# xiaochequdongban.net
KiCad netlist of a schematic drawn in Altium Designer
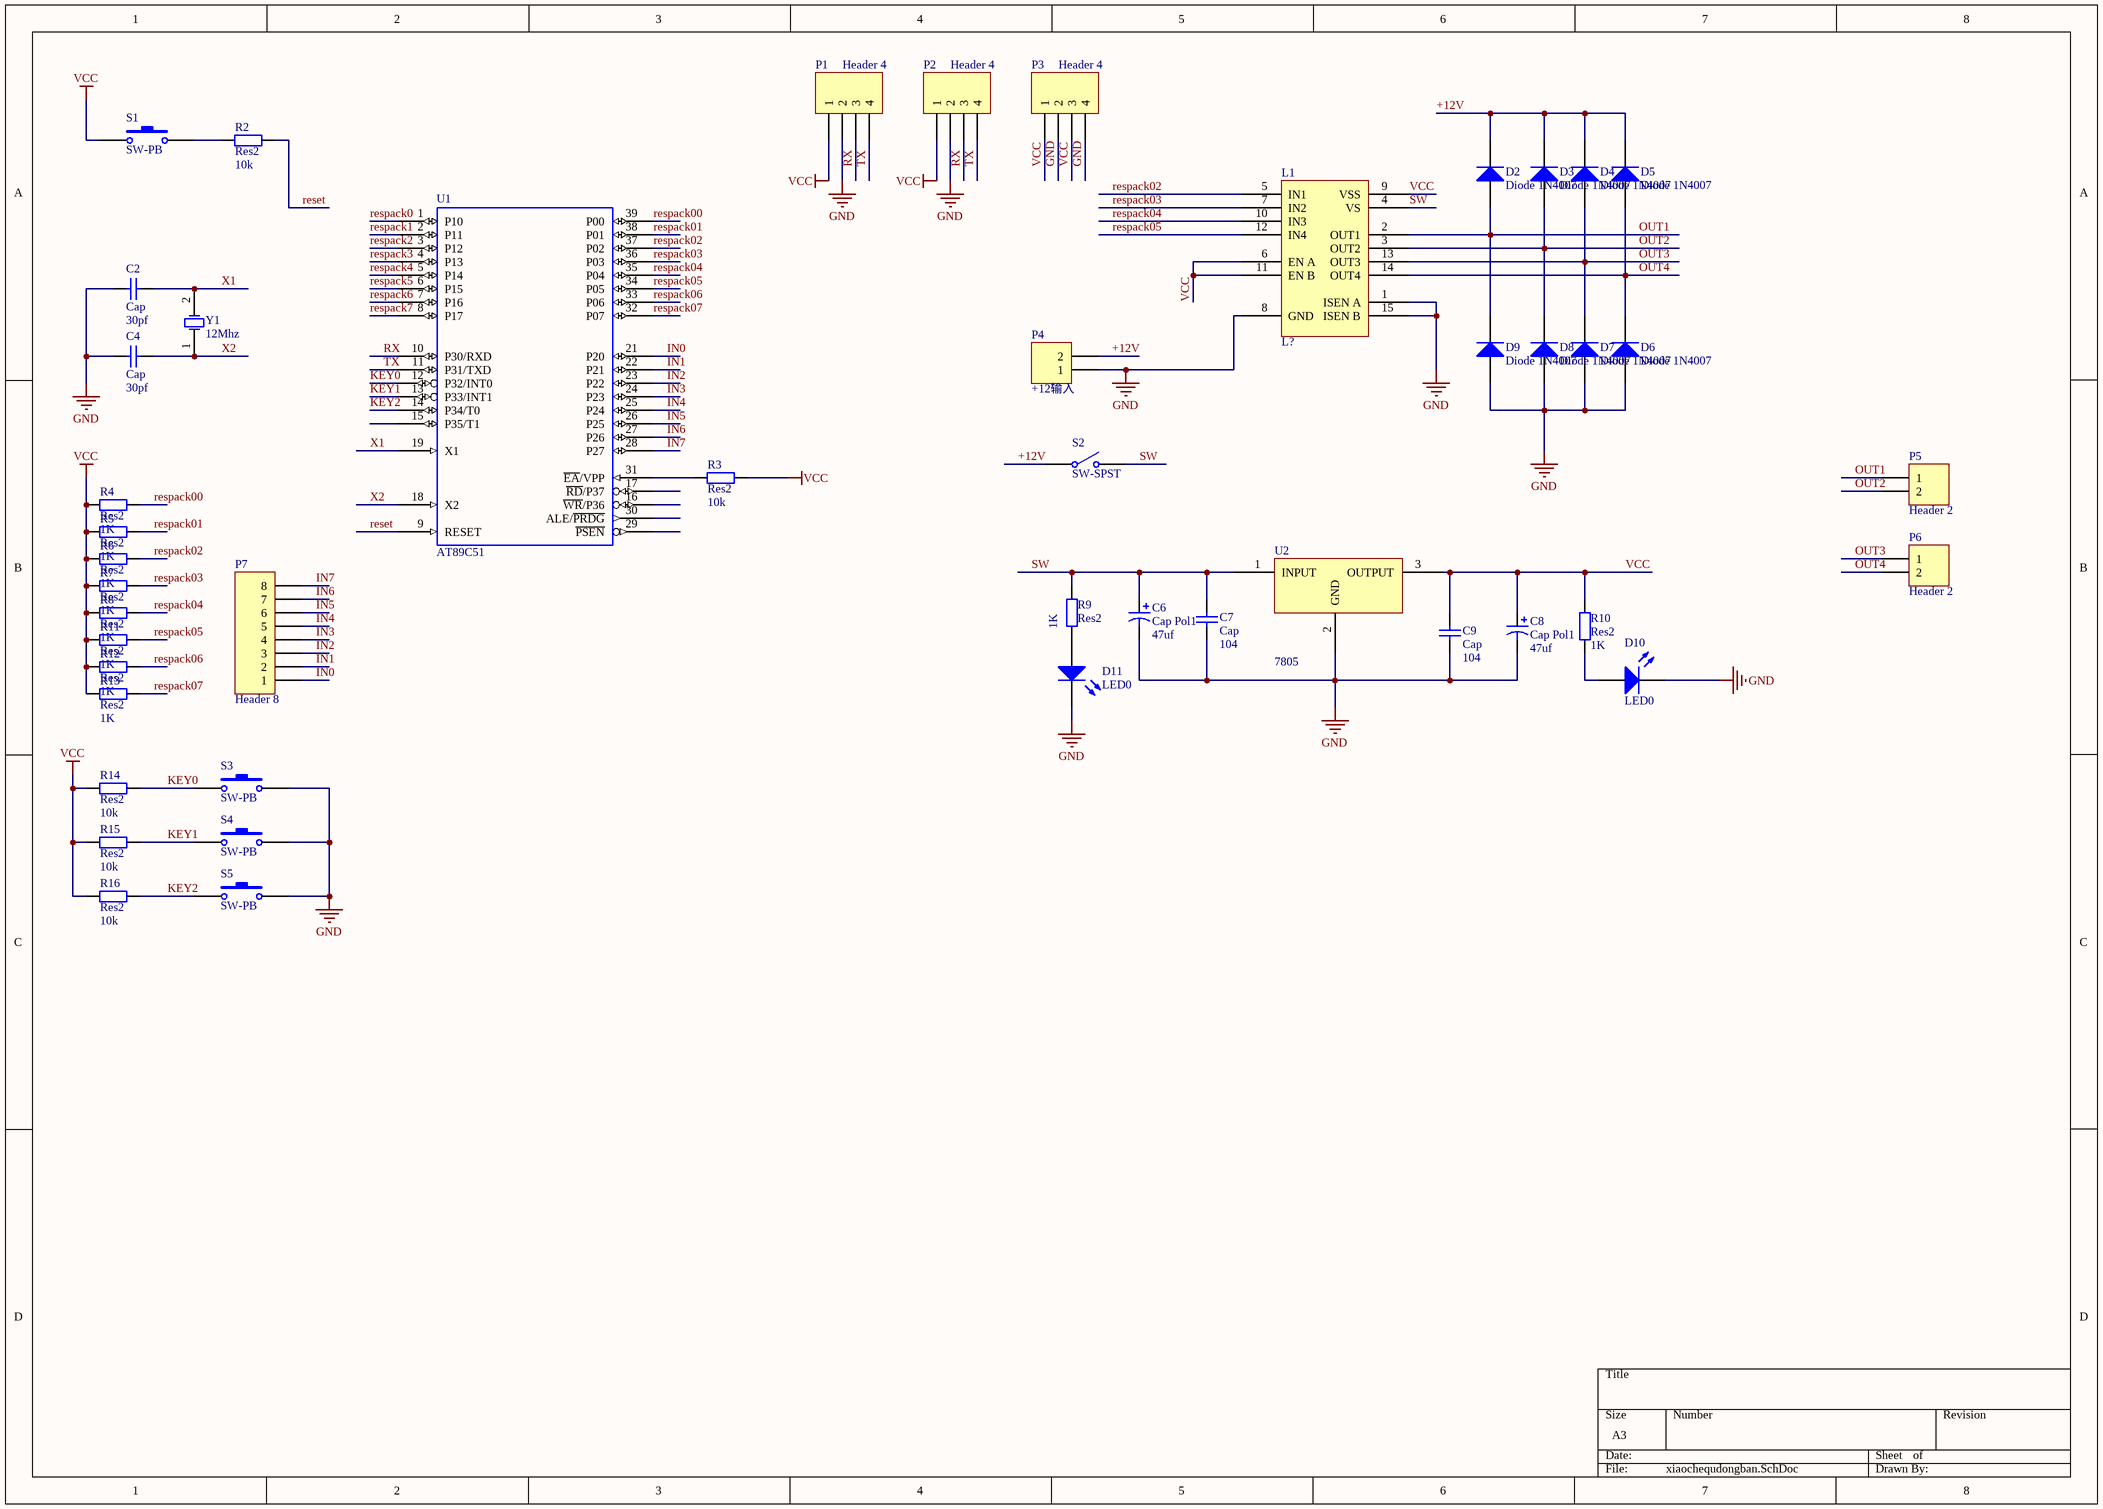
[diagram p0: xiaochequdongban.SchDoc]

(export (version "E")
  (design (tool "Eeschema 10.0.6"))
  (components
    (comp (ref "C2")
      (value "Cap")
      (footprint "RAD0.1")
      (description "Capacitor")
      (fields (field (name "ALTIUM_VALUE") "30pf") (field (name "PUBLISHER") "Altium Limited"))
      (libsource (lib "Miscellaneous Devices") (part "Cap"))
    )
    (comp (ref "C4")
      (value "Cap")
      (footprint "RAD0.1")
      (description "Capacitor")
      (fields (field (name "ALTIUM_VALUE") "30pf") (field (name "PUBLISHER") "Altium Limited"))
      (libsource (lib "Miscellaneous Devices") (part "Cap"))
    )
    (comp (ref "C6")
      (value "Cap Pol1")
      (footprint "CAP-E")
      (description "Polarized Capacitor (Radial)")
      (fields (field (name "ALTIUM_VALUE") "47uf") (field (name "PUBLISHER") "Altium Limited"))
      (libsource (lib "Miscellaneous Devices") (part "Cap Pol1"))
    )
    (comp (ref "C7")
      (value "Cap")
      (footprint "RAD0.1")
      (description "Capacitor")
      (fields (field (name "ALTIUM_VALUE") "104") (field (name "PUBLISHER") "Altium Limited"))
      (libsource (lib "Miscellaneous Devices") (part "Cap"))
    )
    (comp (ref "C8")
      (value "Cap Pol1")
      (footprint "CAP-E")
      (description "Polarized Capacitor (Radial)")
      (fields (field (name "ALTIUM_VALUE") "47uf") (field (name "PUBLISHER") "Altium Limited"))
      (libsource (lib "Miscellaneous Devices") (part "Cap Pol1"))
    )
    (comp (ref "C9")
      (value "Cap")
      (footprint "RAD0.1")
      (description "Capacitor")
      (fields (field (name "ALTIUM_VALUE") "104") (field (name "PUBLISHER") "Altium Limited"))
      (libsource (lib "Miscellaneous Devices") (part "Cap"))
    )
    (comp (ref "D2")
      (value "Diode 1N4007")
      (footprint "DO-41")
      (description "1 Amp General Purpose Rectifier")
      (fields (field (name "PUBLISHER") "Altium Limited"))
      (libsource (lib "Miscellaneous Devices") (part "Diode 1N4007"))
    )
    (comp (ref "D3")
      (value "Diode 1N4007")
      (footprint "DO-41")
      (description "1 Amp General Purpose Rectifier")
      (fields (field (name "PUBLISHER") "Altium Limited"))
      (libsource (lib "Miscellaneous Devices") (part "Diode 1N4007"))
    )
    (comp (ref "D4")
      (value "Diode 1N4007")
      (footprint "DO-41")
      (description "1 Amp General Purpose Rectifier")
      (fields (field (name "PUBLISHER") "Altium Limited"))
      (libsource (lib "Miscellaneous Devices") (part "Diode 1N4007"))
    )
    (comp (ref "D5")
      (value "Diode 1N4007")
      (footprint "DO-41")
      (description "1 Amp General Purpose Rectifier")
      (fields (field (name "PUBLISHER") "Altium Limited"))
      (libsource (lib "Miscellaneous Devices") (part "Diode 1N4007"))
    )
    (comp (ref "D6")
      (value "Diode 1N4007")
      (footprint "DO-41")
      (description "1 Amp General Purpose Rectifier")
      (fields (field (name "PUBLISHER") "Altium Limited"))
      (libsource (lib "Miscellaneous Devices") (part "Diode 1N4007"))
    )
    (comp (ref "D7")
      (value "Diode 1N4007")
      (footprint "DO-41")
      (description "1 Amp General Purpose Rectifier")
      (fields (field (name "PUBLISHER") "Altium Limited"))
      (libsource (lib "Miscellaneous Devices") (part "Diode 1N4007"))
    )
    (comp (ref "D8")
      (value "Diode 1N4007")
      (footprint "DO-41")
      (description "1 Amp General Purpose Rectifier")
      (fields (field (name "PUBLISHER") "Altium Limited"))
      (libsource (lib "Miscellaneous Devices") (part "Diode 1N4007"))
    )
    (comp (ref "D9")
      (value "Diode 1N4007")
      (footprint "DO-41")
      (description "1 Amp General Purpose Rectifier")
      (fields (field (name "PUBLISHER") "Altium Limited"))
      (libsource (lib "Miscellaneous Devices") (part "Diode 1N4007"))
    )
    (comp (ref "D10")
      (value "LED0")
      (footprint "LED")
      (description "Typical INFRARED GaAs LED")
      (fields (field (name "PUBLISHER") "Altium Limited"))
      (libsource (lib "Miscellaneous Devices") (part "LED0"))
    )
    (comp (ref "D11")
      (value "LED0")
      (footprint "LED")
      (description "Typical INFRARED GaAs LED")
      (fields (field (name "PUBLISHER") "Altium Limited"))
      (libsource (lib "Miscellaneous Devices") (part "LED0"))
    )
    (comp (ref "L1") (value "L?") (footprint "L298N") (libsource (lib "常用封装") (part "L298N")))
    (comp (ref "P1")
      (value "Header 4")
      (footprint "HDR1X4")
      (description "Header, 4-Pin")
      (fields (field (name "PUBLISHER") "Altium Limited"))
      (libsource (lib "Miscellaneous Connectors") (part "Header 4"))
    )
    (comp (ref "P2")
      (value "Header 4")
      (footprint "HDR1X4")
      (description "Header, 4-Pin")
      (fields (field (name "PUBLISHER") "Altium Limited"))
      (libsource (lib "Miscellaneous Connectors") (part "Header 4"))
    )
    (comp (ref "P3")
      (value "Header 4")
      (footprint "HDR1X4")
      (description "Header, 4-Pin")
      (fields (field (name "PUBLISHER") "Altium Limited"))
      (libsource (lib "Miscellaneous Connectors") (part "Header 4"))
    )
    (comp (ref "P4")
      (value "+12输入")
      (footprint "HDR1X2")
      (description "Header, 2-Pin")
      (fields (field (name "PUBLISHER") "Altium Limited"))
      (libsource (lib "Miscellaneous Connectors") (part "Header 2"))
    )
    (comp (ref "P5")
      (value "Header 2")
      (footprint "SIP2")
      (description "Header, 2-Pin")
      (fields (field (name "PUBLISHER") "Altium Limited"))
      (libsource (lib "") (part "Header 2_1"))
    )
    (comp (ref "P6")
      (value "Header 2")
      (footprint "HDR1X2")
      (description "Header, 2-Pin")
      (fields (field (name "PUBLISHER") "Altium Limited"))
      (libsource (lib "") (part "Header 2_1"))
    )
    (comp (ref "P7")
      (value "Header 8")
      (footprint "HDR1X8")
      (description "Header, 8-Pin")
      (fields (field (name "PUBLISHER") "Altium Limited"))
      (libsource (lib "Miscellaneous Connectors") (part "Header 8"))
    )
    (comp (ref "R2")
      (value "Res2")
      (footprint "0805")
      (description "Resistor")
      (fields (field (name "ALTIUM_VALUE") "10k") (field (name "PUBLISHER") "Altium Limited"))
      (libsource (lib "") (part "Res2_2"))
    )
    (comp (ref "R3")
      (value "Res2")
      (footprint "0805")
      (description "Resistor")
      (fields (field (name "ALTIUM_VALUE") "10k") (field (name "PUBLISHER") "Altium Limited"))
      (libsource (lib "") (part "Res2_2"))
    )
    (comp (ref "R4")
      (value "Res2")
      (footprint "0805")
      (description "Resistor")
      (fields (field (name "ALTIUM_VALUE") "1K") (field (name "PUBLISHER") "Altium Limited"))
      (libsource (lib "") (part "Res2_2"))
    )
    (comp (ref "R5")
      (value "Res2")
      (footprint "0805")
      (description "Resistor")
      (fields (field (name "ALTIUM_VALUE") "1K") (field (name "PUBLISHER") "Altium Limited"))
      (libsource (lib "") (part "Res2_2"))
    )
    (comp (ref "R6")
      (value "Res2")
      (footprint "0805")
      (description "Resistor")
      (fields (field (name "ALTIUM_VALUE") "1K") (field (name "PUBLISHER") "Altium Limited"))
      (libsource (lib "") (part "Res2_2"))
    )
    (comp (ref "R7")
      (value "Res2")
      (footprint "0805")
      (description "Resistor")
      (fields (field (name "ALTIUM_VALUE") "1K") (field (name "PUBLISHER") "Altium Limited"))
      (libsource (lib "") (part "Res2_2"))
    )
    (comp (ref "R8")
      (value "Res2")
      (footprint "0805")
      (description "Resistor")
      (fields (field (name "ALTIUM_VALUE") "1K") (field (name "PUBLISHER") "Altium Limited"))
      (libsource (lib "") (part "Res2_2"))
    )
    (comp (ref "R9")
      (value "Res2")
      (footprint "AXIAL0.3")
      (description "Resistor")
      (fields (field (name "ALTIUM_VALUE") "1K") (field (name "PUBLISHER") "Altium Limited"))
      (libsource (lib "") (part "Res2_1"))
    )
    (comp (ref "R10")
      (value "Res2")
      (footprint "0805")
      (description "Resistor")
      (fields (field (name "ALTIUM_VALUE") "1K") (field (name "PUBLISHER") "Altium Limited"))
      (libsource (lib "") (part "Res2_1"))
    )
    (comp (ref "R11")
      (value "Res2")
      (footprint "0805")
      (description "Resistor")
      (fields (field (name "ALTIUM_VALUE") "1K") (field (name "PUBLISHER") "Altium Limited"))
      (libsource (lib "") (part "Res2_2"))
    )
    (comp (ref "R12")
      (value "Res2")
      (footprint "0805")
      (description "Resistor")
      (fields (field (name "ALTIUM_VALUE") "1K") (field (name "PUBLISHER") "Altium Limited"))
      (libsource (lib "") (part "Res2_2"))
    )
    (comp (ref "R13")
      (value "Res2")
      (footprint "0805")
      (description "Resistor")
      (fields (field (name "ALTIUM_VALUE") "1K") (field (name "PUBLISHER") "Altium Limited"))
      (libsource (lib "") (part "Res2_2"))
    )
    (comp (ref "R14")
      (value "Res2")
      (footprint "0805")
      (description "Resistor")
      (fields (field (name "ALTIUM_VALUE") "10k") (field (name "PUBLISHER") "Altium Limited"))
      (libsource (lib "Miscellaneous Devices") (part "Res2"))
    )
    (comp (ref "R15")
      (value "Res2")
      (footprint "0805")
      (description "Resistor")
      (fields (field (name "ALTIUM_VALUE") "10k") (field (name "PUBLISHER") "Altium Limited"))
      (libsource (lib "Miscellaneous Devices") (part "Res2"))
    )
    (comp (ref "R16")
      (value "Res2")
      (footprint "0805")
      (description "Resistor")
      (fields (field (name "ALTIUM_VALUE") "10k") (field (name "PUBLISHER") "Altium Limited"))
      (libsource (lib "Miscellaneous Devices") (part "Res2"))
    )
    (comp (ref "S1")
      (value "SW-PB")
      (footprint "KeyA")
      (description "Switch")
      (fields (field (name "PUBLISHER") "Altium Limited"))
      (libsource (lib "Miscellaneous Devices") (part "SW-PB"))
    )
    (comp (ref "S2")
      (value "SW-SPST")
      (footprint "SW-6pin")
      (description "Single-Pole, Single-Throw Switch")
      (fields (field (name "PUBLISHER") "Altium Limited"))
      (libsource (lib "Miscellaneous Devices") (part "SW-SPST"))
    )
    (comp (ref "S3")
      (value "SW-PB")
      (footprint "KeyA")
      (description "Switch")
      (fields (field (name "PUBLISHER") "Altium Limited"))
      (libsource (lib "Miscellaneous Devices") (part "SW-PB"))
    )
    (comp (ref "S4")
      (value "SW-PB")
      (footprint "KeyA")
      (description "Switch")
      (fields (field (name "PUBLISHER") "Altium Limited"))
      (libsource (lib "Miscellaneous Devices") (part "SW-PB"))
    )
    (comp (ref "S5")
      (value "SW-PB")
      (footprint "KeyA")
      (description "Switch")
      (fields (field (name "PUBLISHER") "Altium Limited"))
      (libsource (lib "Miscellaneous Devices") (part "SW-PB"))
    )
    (comp (ref "U1") (value "AT89C51") (footprint "DIP40") (libsource (lib "常用封装") (part "AT89C51")))
    (comp (ref "U2") (value "7805") (footprint "7805") (libsource (lib "常用封装") (part "7805")))
    (comp (ref "Y1")
      (value "12Mhz")
      (footprint "XTAL")
      (description "Crystal Oscillator")
      (fields (field (name "PUBLISHER") "Altium Limited"))
      (libsource (lib "Miscellaneous Devices") (part "XTAL"))
    )
  )
  (nets
    (net (code "1") (name "/+12V") (class "Default")
      (node (ref "D2") (pin "2") (pinfunction "K_2") (pintype "passive"))
      (node (ref "D3") (pin "2") (pinfunction "K_2") (pintype "passive"))
      (node (ref "D4") (pin "2") (pinfunction "K_2") (pintype "passive"))
      (node (ref "D5") (pin "2") (pinfunction "K_2") (pintype "passive"))
      (node (ref "P4") (pin "2") (pinfunction "2_2") (pintype "passive"))
      (node (ref "S2") (pin "1") (pinfunction "COMMON_1") (pintype "passive"))
    )
    (net (code "2") (name "/IN0") (class "Default")
      (node (ref "P7") (pin "1") (pinfunction "1_1") (pintype "passive"))
      (node (ref "U1") (pin "21") (pinfunction "P20_21") (pintype "bidirectional"))
    )
    (net (code "3") (name "/IN1") (class "Default")
      (node (ref "P7") (pin "2") (pinfunction "2_2") (pintype "passive"))
      (node (ref "U1") (pin "22") (pinfunction "P21_22") (pintype "bidirectional"))
    )
    (net (code "4") (name "/IN2") (class "Default")
      (node (ref "P7") (pin "3") (pinfunction "3_3") (pintype "passive"))
      (node (ref "U1") (pin "23") (pinfunction "P22_23") (pintype "bidirectional"))
    )
    (net (code "5") (name "/IN3") (class "Default")
      (node (ref "P7") (pin "4") (pinfunction "4_4") (pintype "passive"))
      (node (ref "U1") (pin "24") (pinfunction "P23_24") (pintype "bidirectional"))
    )
    (net (code "6") (name "/IN4") (class "Default")
      (node (ref "P7") (pin "5") (pinfunction "5_5") (pintype "passive"))
      (node (ref "U1") (pin "25") (pinfunction "P24_25") (pintype "bidirectional"))
    )
    (net (code "7") (name "/IN5") (class "Default")
      (node (ref "P7") (pin "6") (pinfunction "6_6") (pintype "passive"))
      (node (ref "U1") (pin "26") (pinfunction "P25_26") (pintype "bidirectional"))
    )
    (net (code "8") (name "/IN6") (class "Default")
      (node (ref "P7") (pin "7") (pinfunction "7_7") (pintype "passive"))
      (node (ref "U1") (pin "27") (pinfunction "P26_27") (pintype "bidirectional"))
    )
    (net (code "9") (name "/IN7") (class "Default")
      (node (ref "P7") (pin "8") (pinfunction "8_8") (pintype "passive"))
      (node (ref "U1") (pin "28") (pinfunction "P27_28") (pintype "bidirectional"))
    )
    (net (code "10") (name "/KEY0") (class "Default")
      (node (ref "R14") (pin "1") (pinfunction "1_1") (pintype "passive"))
      (node (ref "S3") (pin "1") (pinfunction "1_1") (pintype "passive"))
      (node (ref "U1") (pin "12") (pinfunction "P32/INT0_12") (pintype "bidirectional"))
    )
    (net (code "11") (name "/KEY1") (class "Default")
      (node (ref "R15") (pin "1") (pinfunction "1_1") (pintype "passive"))
      (node (ref "S4") (pin "1") (pinfunction "1_1") (pintype "passive"))
      (node (ref "U1") (pin "13") (pinfunction "P33/INT1_13") (pintype "bidirectional"))
    )
    (net (code "12") (name "/KEY2") (class "Default")
      (node (ref "R16") (pin "1") (pinfunction "1_1") (pintype "passive"))
      (node (ref "S5") (pin "1") (pinfunction "1_1") (pintype "passive"))
      (node (ref "U1") (pin "14") (pinfunction "P34/T0_14") (pintype "bidirectional"))
    )
    (net (code "13") (name "/OUT1") (class "Default")
      (node (ref "D2") (pin "1") (pinfunction "A_1") (pintype "passive"))
      (node (ref "D9") (pin "2") (pinfunction "K_2") (pintype "passive"))
      (node (ref "L1") (pin "2") (pinfunction "OUT1_2") (pintype "passive"))
      (node (ref "P5") (pin "1") (pinfunction "1_1") (pintype "passive"))
    )
    (net (code "14") (name "/OUT2") (class "Default")
      (node (ref "D3") (pin "1") (pinfunction "A_1") (pintype "passive"))
      (node (ref "D8") (pin "2") (pinfunction "K_2") (pintype "passive"))
      (node (ref "L1") (pin "3") (pinfunction "OUT2_3") (pintype "passive"))
      (node (ref "P5") (pin "2") (pinfunction "2_2") (pintype "passive"))
    )
    (net (code "15") (name "/OUT3") (class "Default")
      (node (ref "D4") (pin "1") (pinfunction "A_1") (pintype "passive"))
      (node (ref "D7") (pin "2") (pinfunction "K_2") (pintype "passive"))
      (node (ref "L1") (pin "13") (pinfunction "OUT3_13") (pintype "passive"))
      (node (ref "P6") (pin "1") (pinfunction "1_1") (pintype "passive"))
    )
    (net (code "16") (name "/OUT4") (class "Default")
      (node (ref "D5") (pin "1") (pinfunction "A_1") (pintype "passive"))
      (node (ref "D6") (pin "2") (pinfunction "K_2") (pintype "passive"))
      (node (ref "L1") (pin "14") (pinfunction "OUT4_14") (pintype "passive"))
      (node (ref "P6") (pin "2") (pinfunction "2_2") (pintype "passive"))
    )
    (net (code "17") (name "/RX") (class "Default")
      (node (ref "P1") (pin "3") (pinfunction "3_3") (pintype "passive"))
      (node (ref "P2") (pin "3") (pinfunction "3_3") (pintype "passive"))
      (node (ref "U1") (pin "10") (pinfunction "P30/RXD_10") (pintype "bidirectional"))
    )
    (net (code "18") (name "/SW") (class "Default")
      (node (ref "C6") (pin "1") (pinfunction "1_1") (pintype "passive"))
      (node (ref "C7") (pin "2") (pinfunction "2_2") (pintype "passive"))
      (node (ref "L1") (pin "4") (pinfunction "VS_4") (pintype "passive"))
      (node (ref "R9") (pin "2") (pinfunction "2_2") (pintype "passive"))
      (node (ref "S2") (pin "2") (pinfunction "NO_2") (pintype "passive"))
      (node (ref "U2") (pin "1") (pinfunction "INPUT_1") (pintype "passive"))
    )
    (net (code "19") (name "/TX") (class "Default")
      (node (ref "P1") (pin "4") (pinfunction "4_4") (pintype "passive"))
      (node (ref "P2") (pin "4") (pinfunction "4_4") (pintype "passive"))
      (node (ref "U1") (pin "11") (pinfunction "P31/TXD_11") (pintype "bidirectional"))
    )
    (net (code "20") (name "/X1") (class "Default")
      (node (ref "C2") (pin "1") (pinfunction "1_1") (pintype "passive"))
      (node (ref "U1") (pin "19") (pinfunction "X1_19") (pintype "input"))
      (node (ref "Y1") (pin "2") (pinfunction "OSC2_2") (pintype "passive"))
    )
    (net (code "21") (name "/X2") (class "Default")
      (node (ref "C4") (pin "1") (pinfunction "1_1") (pintype "passive"))
      (node (ref "U1") (pin "18") (pinfunction "X2_18") (pintype "input"))
      (node (ref "Y1") (pin "1") (pinfunction "OSC1_1") (pintype "passive"))
    )
    (net (code "22") (name "/reset") (class "Default")
      (node (ref "R2") (pin "2") (pinfunction "2_2") (pintype "passive"))
      (node (ref "U1") (pin "9") (pinfunction "RESET_9") (pintype "input"))
    )
    (net (code "23") (name "/respack00") (class "Default")
      (node (ref "R4") (pin "2") (pinfunction "2_2") (pintype "passive"))
      (node (ref "U1") (pin "39") (pinfunction "P00_39") (pintype "bidirectional"))
    )
    (net (code "24") (name "/respack0") (class "Default")
      (node (ref "U1") (pin "1") (pinfunction "P10_1") (pintype "bidirectional"))
    )
    (net (code "25") (name "/respack1") (class "Default")
      (node (ref "U1") (pin "2") (pinfunction "P11_2") (pintype "bidirectional"))
    )
    (net (code "26") (name "/respack01") (class "Default")
      (node (ref "R5") (pin "2") (pinfunction "2_2") (pintype "passive"))
      (node (ref "U1") (pin "38") (pinfunction "P01_38") (pintype "bidirectional"))
    )
    (net (code "27") (name "/respack2") (class "Default")
      (node (ref "U1") (pin "3") (pinfunction "P12_3") (pintype "bidirectional"))
    )
    (net (code "28") (name "/respack02") (class "Default")
      (node (ref "L1") (pin "5") (pinfunction "IN1_5") (pintype "passive"))
      (node (ref "R6") (pin "2") (pinfunction "2_2") (pintype "passive"))
      (node (ref "U1") (pin "37") (pinfunction "P02_37") (pintype "bidirectional"))
    )
    (net (code "29") (name "/respack03") (class "Default")
      (node (ref "L1") (pin "7") (pinfunction "IN2_7") (pintype "passive"))
      (node (ref "R7") (pin "2") (pinfunction "2_2") (pintype "passive"))
      (node (ref "U1") (pin "36") (pinfunction "P03_36") (pintype "bidirectional"))
    )
    (net (code "30") (name "/respack3") (class "Default")
      (node (ref "U1") (pin "4") (pinfunction "P13_4") (pintype "bidirectional"))
    )
    (net (code "31") (name "/respack4") (class "Default")
      (node (ref "U1") (pin "5") (pinfunction "P14_5") (pintype "bidirectional"))
    )
    (net (code "32") (name "/respack04") (class "Default")
      (node (ref "L1") (pin "10") (pinfunction "IN3_10") (pintype "passive"))
      (node (ref "R8") (pin "2") (pinfunction "2_2") (pintype "passive"))
      (node (ref "U1") (pin "35") (pinfunction "P04_35") (pintype "bidirectional"))
    )
    (net (code "33") (name "/respack05") (class "Default")
      (node (ref "L1") (pin "12") (pinfunction "IN4_12") (pintype "passive"))
      (node (ref "R11") (pin "2") (pinfunction "2_2") (pintype "passive"))
      (node (ref "U1") (pin "34") (pinfunction "P05_34") (pintype "bidirectional"))
    )
    (net (code "34") (name "/respack5") (class "Default")
      (node (ref "U1") (pin "6") (pinfunction "P15_6") (pintype "bidirectional"))
    )
    (net (code "35") (name "/respack6") (class "Default")
      (node (ref "U1") (pin "7") (pinfunction "P16_7") (pintype "bidirectional"))
    )
    (net (code "36") (name "/respack06") (class "Default")
      (node (ref "R12") (pin "2") (pinfunction "2_2") (pintype "passive"))
      (node (ref "U1") (pin "33") (pinfunction "P06_33") (pintype "bidirectional"))
    )
    (net (code "37") (name "/respack7") (class "Default")
      (node (ref "U1") (pin "8") (pinfunction "P17_8") (pintype "bidirectional"))
    )
    (net (code "38") (name "/respack07") (class "Default")
      (node (ref "R13") (pin "2") (pinfunction "2_2") (pintype "passive"))
      (node (ref "U1") (pin "32") (pinfunction "P07_32") (pintype "bidirectional"))
    )
    (net (code "39") (name "GND") (class "Default")
      (node (ref "C2") (pin "2") (pinfunction "2_2") (pintype "passive"))
      (node (ref "C4") (pin "2") (pinfunction "2_2") (pintype "passive"))
      (node (ref "C6") (pin "2") (pinfunction "2_2") (pintype "passive"))
      (node (ref "C7") (pin "1") (pinfunction "1_1") (pintype "passive"))
      (node (ref "C8") (pin "2") (pinfunction "2_2") (pintype "passive"))
      (node (ref "C9") (pin "1") (pinfunction "1_1") (pintype "passive"))
      (node (ref "D10") (pin "2") (pinfunction "K_2") (pintype "passive"))
      (node (ref "D11") (pin "2") (pinfunction "K_2") (pintype "passive"))
      (node (ref "D6") (pin "1") (pinfunction "A_1") (pintype "passive"))
      (node (ref "D7") (pin "1") (pinfunction "A_1") (pintype "passive"))
      (node (ref "D8") (pin "1") (pinfunction "A_1") (pintype "passive"))
      (node (ref "D9") (pin "1") (pinfunction "A_1") (pintype "passive"))
      (node (ref "L1") (pin "1") (pinfunction "ISEN_A_1") (pintype "passive"))
      (node (ref "L1") (pin "15") (pinfunction "ISEN_B_15") (pintype "passive"))
      (node (ref "L1") (pin "8") (pinfunction "GND_8") (pintype "passive"))
      (node (ref "P1") (pin "2") (pinfunction "2_2") (pintype "passive"))
      (node (ref "P2") (pin "2") (pinfunction "2_2") (pintype "passive"))
      (node (ref "P3") (pin "2") (pinfunction "2_2") (pintype "passive"))
      (node (ref "P3") (pin "4") (pinfunction "4_4") (pintype "passive"))
      (node (ref "P4") (pin "1") (pinfunction "1_1") (pintype "passive"))
      (node (ref "S3") (pin "2") (pinfunction "2_2") (pintype "passive"))
      (node (ref "S4") (pin "2") (pinfunction "2_2") (pintype "passive"))
      (node (ref "S5") (pin "2") (pinfunction "2_2") (pintype "passive"))
      (node (ref "U1") (pin "20") (pinfunction "GND_20") (pintype "power_in"))
      (node (ref "U2") (pin "2") (pinfunction "GND_2") (pintype "passive"))
    )
    (net (code "40") (name "Net-(D10-A)") (class "Default")
      (node (ref "D10") (pin "1") (pinfunction "A_1") (pintype "passive"))
      (node (ref "R10") (pin "1") (pinfunction "1_1") (pintype "passive"))
    )
    (net (code "41") (name "Net-(D11-A)") (class "Default")
      (node (ref "D11") (pin "1") (pinfunction "A_1") (pintype "passive"))
      (node (ref "R9") (pin "1") (pinfunction "1_1") (pintype "passive"))
    )
    (net (code "42") (name "Net-(R2-Pad1)") (class "Default")
      (node (ref "R2") (pin "1") (pinfunction "1_1") (pintype "passive"))
      (node (ref "S1") (pin "2") (pinfunction "2_2") (pintype "passive"))
    )
    (net (code "43") (name "Net-(U1-~{EA}{slash}VPP)") (class "Default")
      (node (ref "R3") (pin "1") (pinfunction "1_1") (pintype "passive"))
      (node (ref "U1") (pin "31") (pinfunction "~{EA}/VPP_31") (pintype "input"))
    )
    (net (code "44") (name "VCC") (class "Default")
      (node (ref "C8") (pin "1") (pinfunction "1_1") (pintype "passive"))
      (node (ref "C9") (pin "2") (pinfunction "2_2") (pintype "passive"))
      (node (ref "L1") (pin "11") (pinfunction "EN_B_11") (pintype "passive"))
      (node (ref "L1") (pin "6") (pinfunction "EN_A_6") (pintype "passive"))
      (node (ref "L1") (pin "9") (pinfunction "VSS_9") (pintype "passive"))
      (node (ref "P1") (pin "1") (pinfunction "1_1") (pintype "passive"))
      (node (ref "P2") (pin "1") (pinfunction "1_1") (pintype "passive"))
      (node (ref "P3") (pin "1") (pinfunction "1_1") (pintype "passive"))
      (node (ref "P3") (pin "3") (pinfunction "3_3") (pintype "passive"))
      (node (ref "R10") (pin "2") (pinfunction "2_2") (pintype "passive"))
      (node (ref "R11") (pin "1") (pinfunction "1_1") (pintype "passive"))
      (node (ref "R12") (pin "1") (pinfunction "1_1") (pintype "passive"))
      (node (ref "R13") (pin "1") (pinfunction "1_1") (pintype "passive"))
      (node (ref "R14") (pin "2") (pinfunction "2_2") (pintype "passive"))
      (node (ref "R15") (pin "2") (pinfunction "2_2") (pintype "passive"))
      (node (ref "R16") (pin "2") (pinfunction "2_2") (pintype "passive"))
      (node (ref "R3") (pin "2") (pinfunction "2_2") (pintype "passive"))
      (node (ref "R4") (pin "1") (pinfunction "1_1") (pintype "passive"))
      (node (ref "R5") (pin "1") (pinfunction "1_1") (pintype "passive"))
      (node (ref "R6") (pin "1") (pinfunction "1_1") (pintype "passive"))
      (node (ref "R7") (pin "1") (pinfunction "1_1") (pintype "passive"))
      (node (ref "R8") (pin "1") (pinfunction "1_1") (pintype "passive"))
      (node (ref "S1") (pin "1") (pinfunction "1_1") (pintype "passive"))
      (node (ref "U1") (pin "40") (pinfunction "VCC_40") (pintype "power_in"))
      (node (ref "U2") (pin "3") (pinfunction "OUTPUT_3") (pintype "passive"))
    )
    (net (code "45") (name "unconnected-(U1-ALE{slash}~{PRDG}-Pad30)") (class "Default")
      (node (ref "U1") (pin "30") (pinfunction "ALE/~{PRDG}_30") (pintype "output"))
    )
    (net (code "46") (name "unconnected-(U1-P35{slash}T1-Pad15)") (class "Default")
      (node (ref "U1") (pin "15") (pinfunction "P35/T1_15") (pintype "bidirectional"))
    )
    (net (code "47") (name "unconnected-(U1-~{PSEN}-Pad29)") (class "Default")
      (node (ref "U1") (pin "29") (pinfunction "~{PSEN}_29") (pintype "output"))
    )
    (net (code "48") (name "unconnected-(U1-~{RD}{slash}P37-Pad17)") (class "Default")
      (node (ref "U1") (pin "17") (pinfunction "~{RD}/P37_17") (pintype "bidirectional"))
    )
    (net (code "49") (name "unconnected-(U1-~{WR}{slash}P36-Pad16)") (class "Default")
      (node (ref "U1") (pin "16") (pinfunction "~{WR}/P36_16") (pintype "bidirectional"))
    )
  )
)
